# IOExpander.net
KiCad netlist of a schematic drawn in Altium Designer
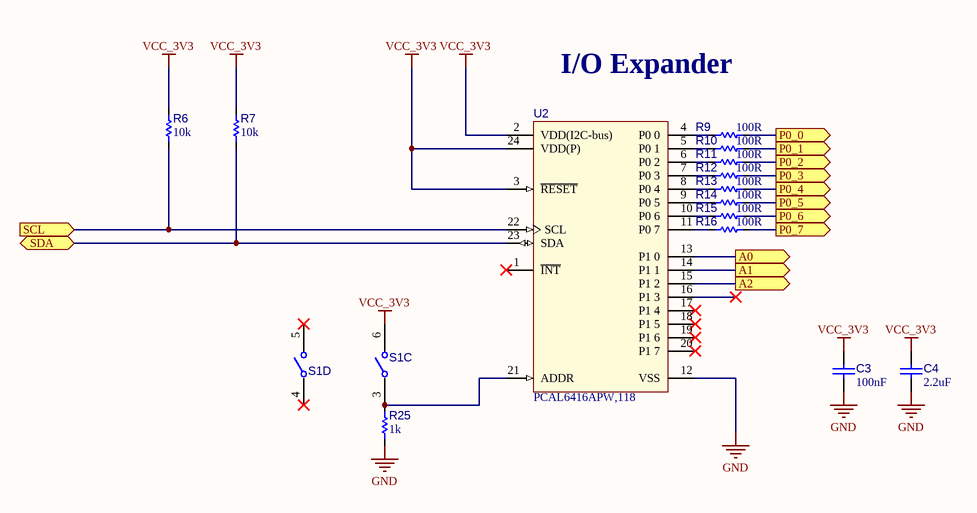
[diagram p0: IOExpander.SchDoc]

(export (version "E")
  (design (tool "Eeschema 10.0.6"))
  (components
    (comp (ref "C3")
      (value "100nF")
      (footprint "C_1608[0603]")
      (description "Capacitor type 1")
      (fields (field (name "TOLERANCE") "10%") (field (name "Comment") "CAP CER 100nF 50V 0603"))
      (libsource (lib "TEP-AltiumLib-Passives-RLC") (part "capacitor"))
    )
    (comp (ref "C4")
      (value "2.2uF")
      (footprint "C_1608[0603]")
      (description "Capacitor type 1")
      (fields (field (name "TOLERANCE") "10%") (field (name "Comment") "CAP CER 2.2uF 10V X7R 0603"))
      (libsource (lib "TEP-AltiumLib-Passives-RLC") (part "capacitor"))
    )
    (comp (ref "R6")
      (value "10k")
      (footprint "R_1608[0603]")
      (description "Resistor type 1")
      (fields (field (name "TOLERANCE") "1%") (field (name "Comment") "Res 10k 1% 0603"))
      (libsource (lib "TEP-AltiumLib-Passives-RLC") (part "resistor"))
    )
    (comp (ref "R7")
      (value "10k")
      (footprint "R_1608[0603]")
      (description "Resistor type 1")
      (fields (field (name "TOLERANCE") "1%") (field (name "Comment") "Res 10k 1% 0603"))
      (libsource (lib "TEP-AltiumLib-Passives-RLC") (part "resistor"))
    )
    (comp (ref "R9")
      (value "100R")
      (footprint "R_1608[0603]")
      (description "Resistor type 1")
      (fields (field (name "TOLERANCE") "1%") (field (name "Comment") "Res 100R 1% 0603"))
      (libsource (lib "TEP-AltiumLib-Passives-RLC") (part "resistor"))
    )
    (comp (ref "R10")
      (value "100R")
      (footprint "R_1608[0603]")
      (description "Resistor type 1")
      (fields (field (name "TOLERANCE") "1%") (field (name "Comment") "Res 100R 1% 0603"))
      (libsource (lib "TEP-AltiumLib-Passives-RLC") (part "resistor"))
    )
    (comp (ref "R11")
      (value "100R")
      (footprint "R_1608[0603]")
      (description "Resistor type 1")
      (fields (field (name "TOLERANCE") "1%") (field (name "Comment") "Res 100R 1% 0603"))
      (libsource (lib "TEP-AltiumLib-Passives-RLC") (part "resistor"))
    )
    (comp (ref "R12")
      (value "100R")
      (footprint "R_1608[0603]")
      (description "Resistor type 1")
      (fields (field (name "TOLERANCE") "1%") (field (name "Comment") "Res 100R 1% 0603"))
      (libsource (lib "TEP-AltiumLib-Passives-RLC") (part "resistor"))
    )
    (comp (ref "R13")
      (value "100R")
      (footprint "R_1608[0603]")
      (description "Resistor type 1")
      (fields (field (name "TOLERANCE") "1%") (field (name "Comment") "Res 100R 1% 0603"))
      (libsource (lib "TEP-AltiumLib-Passives-RLC") (part "resistor"))
    )
    (comp (ref "R14")
      (value "100R")
      (footprint "R_1608[0603]")
      (description "Resistor type 1")
      (fields (field (name "TOLERANCE") "1%") (field (name "Comment") "Res 100R 1% 0603"))
      (libsource (lib "TEP-AltiumLib-Passives-RLC") (part "resistor"))
    )
    (comp (ref "R15")
      (value "100R")
      (footprint "R_1608[0603]")
      (description "Resistor type 1")
      (fields (field (name "TOLERANCE") "1%") (field (name "Comment") "Res 100R 1% 0603"))
      (libsource (lib "TEP-AltiumLib-Passives-RLC") (part "resistor"))
    )
    (comp (ref "R16")
      (value "100R")
      (footprint "R_1608[0603]")
      (description "Resistor type 1")
      (fields (field (name "TOLERANCE") "1%") (field (name "Comment") "Res 100R 1% 0603"))
      (libsource (lib "TEP-AltiumLib-Passives-RLC") (part "resistor"))
    )
    (comp (ref "R25")
      (value "1k")
      (footprint "R_1608[0603]")
      (description "Resistor type 1")
      (fields (field (name "TOLERANCE") "1%") (field (name "Comment") "Res 1k 1% 0603"))
      (libsource (lib "TEP-AltiumLib-Passives-RLC") (part "resistor"))
    )
    (comp (ref "S1")
      (value "DSHP04TSGER")
      (footprint "S_DIP_SWITCH_50MIL_4POS")
      (description "SWITCH DIP SLIDE SPST 25MA 24V, pitch 1.27mm, height 1.55mm")
      (libsource (lib "TEP-AltiumLib") (part "SW_DIP_50MIL_4POS"))
    )
    (comp (ref "U2")
      (value "PCAL6416APW,118")
      (footprint "U_TSSOP24_SOT355-1-IPC_B")
      (description "IC I/O EXPANDER 16BIT 24TSSOP")
      (libsource (lib "TEP-AltiumLib-ICs") (part "U_PCAL6416APW"))
    )
  )
  (nets
    (net (code "1") (name "/A0") (class "Default")
      (node (ref "U2") (pin "13") (pinfunction "P1_0_13") (pintype "passive"))
    )
    (net (code "2") (name "/A1") (class "Default")
      (node (ref "U2") (pin "14") (pinfunction "P1_1_14") (pintype "passive"))
    )
    (net (code "3") (name "/A2") (class "Default")
      (node (ref "U2") (pin "15") (pinfunction "P1_2_15") (pintype "passive"))
    )
    (net (code "4") (name "/P0_0") (class "Default")
      (node (ref "R9") (pin "2") (pinfunction "2_2") (pintype "passive"))
    )
    (net (code "5") (name "/P0_1") (class "Default")
      (node (ref "R10") (pin "2") (pinfunction "2_2") (pintype "passive"))
    )
    (net (code "6") (name "/P0_2") (class "Default")
      (node (ref "R11") (pin "2") (pinfunction "2_2") (pintype "passive"))
    )
    (net (code "7") (name "/P0_3") (class "Default")
      (node (ref "R12") (pin "2") (pinfunction "2_2") (pintype "passive"))
    )
    (net (code "8") (name "/P0_4") (class "Default")
      (node (ref "R13") (pin "2") (pinfunction "2_2") (pintype "passive"))
    )
    (net (code "9") (name "/P0_5") (class "Default")
      (node (ref "R14") (pin "2") (pinfunction "2_2") (pintype "passive"))
    )
    (net (code "10") (name "/P0_6") (class "Default")
      (node (ref "R15") (pin "2") (pinfunction "2_2") (pintype "passive"))
    )
    (net (code "11") (name "/P0_7") (class "Default")
      (node (ref "R16") (pin "2") (pinfunction "2_2") (pintype "passive"))
    )
    (net (code "12") (name "/SCL") (class "Default")
      (node (ref "R6") (pin "1") (pinfunction "1_1") (pintype "passive"))
      (node (ref "U2") (pin "22") (pinfunction "SCL_22") (pintype "input"))
    )
    (net (code "13") (name "/SDA") (class "Default")
      (node (ref "R7") (pin "1") (pinfunction "1_1") (pintype "passive"))
      (node (ref "U2") (pin "23") (pinfunction "SDA_23") (pintype "bidirectional"))
    )
    (net (code "14") (name "GND") (class "Default")
      (node (ref "C3") (pin "1") (pinfunction "1_1") (pintype "passive"))
      (node (ref "C4") (pin "1") (pinfunction "1_1") (pintype "passive"))
      (node (ref "R25") (pin "1") (pinfunction "1_1") (pintype "passive"))
      (node (ref "U2") (pin "12") (pinfunction "VSS_12") (pintype "power_in"))
    )
    (net (code "15") (name "Net-(U2-ADDR)") (class "Default")
      (node (ref "R25") (pin "2") (pinfunction "2_2") (pintype "passive"))
      (node (ref "S1") (pin "3") (pinfunction "3_3") (pintype "passive"))
      (node (ref "U2") (pin "21") (pinfunction "ADDR_21") (pintype "input"))
    )
    (net (code "16") (name "Net-(U2-P0_0)") (class "Default")
      (node (ref "R9") (pin "1") (pinfunction "1_1") (pintype "passive"))
      (node (ref "U2") (pin "4") (pinfunction "P0_0_4") (pintype "passive"))
    )
    (net (code "17") (name "Net-(U2-P0_1)") (class "Default")
      (node (ref "R10") (pin "1") (pinfunction "1_1") (pintype "passive"))
      (node (ref "U2") (pin "5") (pinfunction "P0_1_5") (pintype "passive"))
    )
    (net (code "18") (name "Net-(U2-P0_2)") (class "Default")
      (node (ref "R11") (pin "1") (pinfunction "1_1") (pintype "passive"))
      (node (ref "U2") (pin "6") (pinfunction "P0_2_6") (pintype "passive"))
    )
    (net (code "19") (name "Net-(U2-P0_3)") (class "Default")
      (node (ref "R12") (pin "1") (pinfunction "1_1") (pintype "passive"))
      (node (ref "U2") (pin "7") (pinfunction "P0_3_7") (pintype "passive"))
    )
    (net (code "20") (name "Net-(U2-P0_4)") (class "Default")
      (node (ref "R13") (pin "1") (pinfunction "1_1") (pintype "passive"))
      (node (ref "U2") (pin "8") (pinfunction "P0_4_8") (pintype "passive"))
    )
    (net (code "21") (name "Net-(U2-P0_5)") (class "Default")
      (node (ref "R14") (pin "1") (pinfunction "1_1") (pintype "passive"))
      (node (ref "U2") (pin "9") (pinfunction "P0_5_9") (pintype "passive"))
    )
    (net (code "22") (name "Net-(U2-P0_6)") (class "Default")
      (node (ref "R15") (pin "1") (pinfunction "1_1") (pintype "passive"))
      (node (ref "U2") (pin "10") (pinfunction "P0_6_10") (pintype "passive"))
    )
    (net (code "23") (name "Net-(U2-P0_7)") (class "Default")
      (node (ref "R16") (pin "1") (pinfunction "1_1") (pintype "passive"))
      (node (ref "U2") (pin "11") (pinfunction "P0_7_11") (pintype "passive"))
    )
    (net (code "24") (name "VCC_3V3") (class "Default")
      (node (ref "C3") (pin "2") (pinfunction "2_2") (pintype "passive"))
      (node (ref "C4") (pin "2") (pinfunction "2_2") (pintype "passive"))
      (node (ref "R6") (pin "2") (pinfunction "2_2") (pintype "passive"))
      (node (ref "R7") (pin "2") (pinfunction "2_2") (pintype "passive"))
      (node (ref "S1") (pin "6") (pinfunction "6_6") (pintype "passive"))
      (node (ref "U2") (pin "2") (pinfunction "VDD(I2C-bus)_2") (pintype "power_in"))
      (node (ref "U2") (pin "24") (pinfunction "VDD(P)_24") (pintype "power_in"))
      (node (ref "U2") (pin "3") (pinfunction "~{RESET}_3") (pintype "input"))
    )
    (net (code "25") (name "unconnected-(S1-Pad4)") (class "Default")
      (node (ref "S1") (pin "4") (pinfunction "4_4") (pintype "passive+no_connect"))
    )
    (net (code "26") (name "unconnected-(S1-Pad5)") (class "Default")
      (node (ref "S1") (pin "5") (pinfunction "5_5") (pintype "passive+no_connect"))
    )
    (net (code "27") (name "unconnected-(U2-P1_3-Pad16)") (class "Default")
      (node (ref "U2") (pin "16") (pinfunction "P1_3_16") (pintype "passive+no_connect"))
    )
    (net (code "28") (name "unconnected-(U2-P1_4-Pad17)") (class "Default")
      (node (ref "U2") (pin "17") (pinfunction "P1_4_17") (pintype "passive+no_connect"))
    )
    (net (code "29") (name "unconnected-(U2-P1_5-Pad18)") (class "Default")
      (node (ref "U2") (pin "18") (pinfunction "P1_5_18") (pintype "passive+no_connect"))
    )
    (net (code "30") (name "unconnected-(U2-P1_6-Pad19)") (class "Default")
      (node (ref "U2") (pin "19") (pinfunction "P1_6_19") (pintype "passive+no_connect"))
    )
    (net (code "31") (name "unconnected-(U2-P1_7-Pad20)") (class "Default")
      (node (ref "U2") (pin "20") (pinfunction "P1_7_20") (pintype "passive+no_connect"))
    )
    (net (code "32") (name "unconnected-(U2-~{INT}-Pad1)") (class "Default")
      (node (ref "U2") (pin "1") (pinfunction "~{INT}_1") (pintype "open_collector+no_connect"))
    )
  )
)
